# sdcard.net
KiCad netlist of a schematic drawn in EAGLE
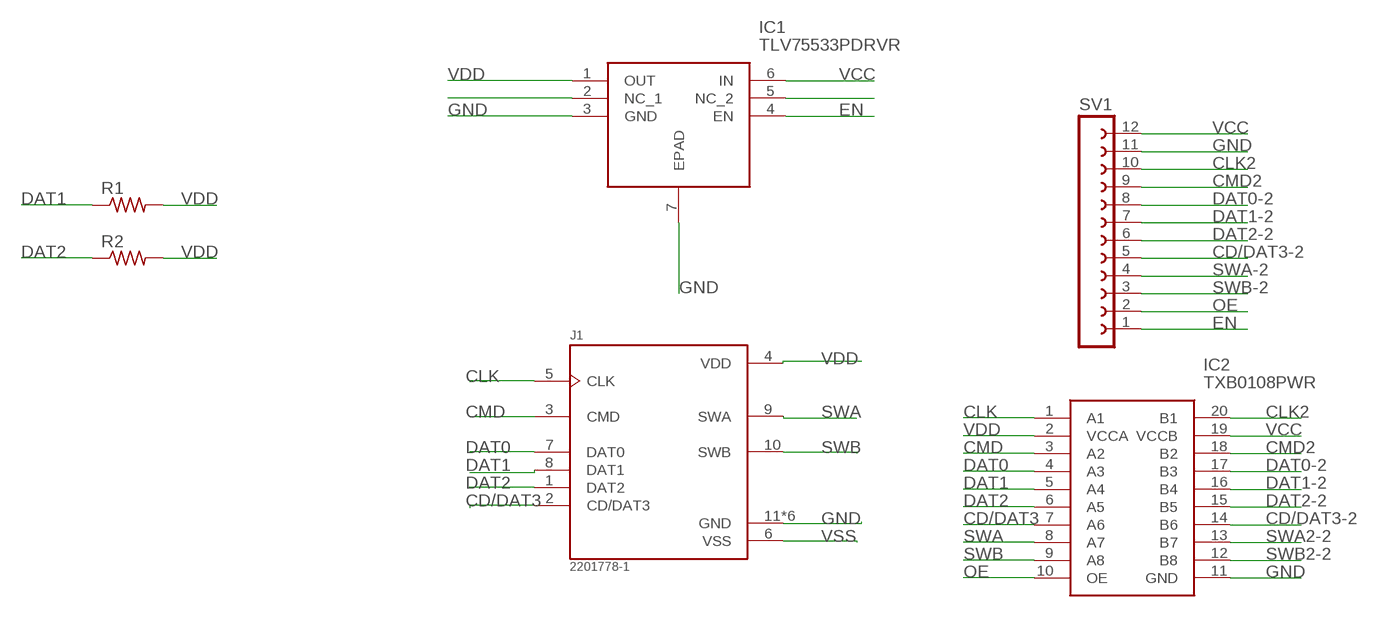
[diagram p0: schematic, sheet 1]

(export (version "E")
  (design (tool "Eeschema 10.0.6"))
  (components
    (comp (ref "IC1")
      (value "TLV75533PDRVR")
      (footprint "eagle-import:SON65P200X200X80-7N")
      (fields (field (name "MOUSER_PART_NUMBER") "595-TLV75533PDRVR"))
      (libsource (lib "eagle-import") (part "TLV75533PDRVR"))
    )
    (comp (ref "IC2")
      (value "TXB0108PWR")
      (footprint "eagle-import:SOP65P640X120-20N")
      (fields (field (name "MOUSER_PART_NUMBER") "595-TXB0108PWR") (field (name "RS_PART_NUMBER") "7094614P"))
      (libsource (lib "eagle-import") (part "TXB0108PWR"))
    )
    (comp (ref "J1")
      (value "2201778-1")
      (footprint "eagle-import:TE_2201778-1")
      (fields (field (name "MF") "TE Connectivity"))
      (libsource (lib "eagle-import") (part "2201778-1"))
    )
    (comp (ref "R1")
      (value "R-US_R0603")
      (footprint "eagle-import:R0603")
      (libsource (lib "eagle-import") (part "R-US_R0603"))
    )
    (comp (ref "R2")
      (value "R-US_R0603")
      (footprint "eagle-import:R0603")
      (libsource (lib "eagle-import") (part "R-US_R0603"))
    )
    (comp (ref "SV1")
      (value "FE12-1")
      (footprint "eagle-import:FE12")
      (libsource (lib "eagle-import") (part "FE12-1"))
    )
  )
  (nets
    (net (code "1") (name "/CD{slash}DAT3") (class "Default")
      (node (ref "IC2") (pin "7") (pinfunction "A6_7") (pintype "bidirectional"))
      (node (ref "J1") (pin "2") (pinfunction "CD/DAT3_2") (pintype "bidirectional"))
    )
    (net (code "2") (name "/CD{slash}DAT3-2") (class "Default")
      (node (ref "IC2") (pin "14") (pinfunction "B6_14") (pintype "bidirectional"))
      (node (ref "SV1") (pin "5") (pinfunction "5_5") (pintype "passive"))
    )
    (net (code "3") (name "/CLK") (class "Default")
      (node (ref "IC2") (pin "1") (pinfunction "A1_1") (pintype "bidirectional"))
      (node (ref "J1") (pin "5") (pinfunction "CLK_5") (pintype "input"))
    )
    (net (code "4") (name "/CLK2") (class "Default")
      (node (ref "IC2") (pin "20") (pinfunction "B1_20") (pintype "bidirectional"))
      (node (ref "SV1") (pin "10") (pinfunction "10_10") (pintype "passive"))
    )
    (net (code "5") (name "/CMD") (class "Default")
      (node (ref "IC2") (pin "3") (pinfunction "A2_3") (pintype "bidirectional"))
      (node (ref "J1") (pin "3") (pinfunction "CMD_3") (pintype "bidirectional"))
    )
    (net (code "6") (name "/CMD2") (class "Default")
      (node (ref "IC2") (pin "18") (pinfunction "B2_18") (pintype "bidirectional"))
      (node (ref "SV1") (pin "9") (pinfunction "9_9") (pintype "passive"))
    )
    (net (code "7") (name "/DAT0") (class "Default")
      (node (ref "IC2") (pin "4") (pinfunction "A3_4") (pintype "bidirectional"))
      (node (ref "J1") (pin "7") (pinfunction "DAT0_7") (pintype "bidirectional"))
    )
    (net (code "8") (name "/DAT0-2") (class "Default")
      (node (ref "IC2") (pin "17") (pinfunction "B3_17") (pintype "bidirectional"))
      (node (ref "SV1") (pin "8") (pinfunction "8_8") (pintype "passive"))
    )
    (net (code "9") (name "/DAT1") (class "Default")
      (node (ref "IC2") (pin "5") (pinfunction "A4_5") (pintype "bidirectional"))
      (node (ref "J1") (pin "8") (pinfunction "DAT1_8") (pintype "bidirectional"))
      (node (ref "R1") (pin "1") (pinfunction "1_1") (pintype "passive"))
    )
    (net (code "10") (name "/DAT1-2") (class "Default")
      (node (ref "IC2") (pin "16") (pinfunction "B4_16") (pintype "bidirectional"))
      (node (ref "SV1") (pin "7") (pinfunction "7_7") (pintype "passive"))
    )
    (net (code "11") (name "/DAT2") (class "Default")
      (node (ref "IC2") (pin "6") (pinfunction "A5_6") (pintype "bidirectional"))
      (node (ref "J1") (pin "1") (pinfunction "DAT2_1") (pintype "bidirectional"))
      (node (ref "R2") (pin "1") (pinfunction "1_1") (pintype "passive"))
    )
    (net (code "12") (name "/DAT2-2") (class "Default")
      (node (ref "IC2") (pin "15") (pinfunction "B5_15") (pintype "bidirectional"))
      (node (ref "SV1") (pin "6") (pinfunction "6_6") (pintype "passive"))
    )
    (net (code "13") (name "/EN") (class "Default")
      (node (ref "IC1") (pin "4") (pinfunction "EN_4") (pintype "bidirectional"))
      (node (ref "SV1") (pin "1") (pinfunction "1_1") (pintype "passive"))
    )
    (net (code "14") (name "/GND") (class "Default")
      (node (ref "IC1") (pin "3") (pinfunction "GND_3") (pintype "bidirectional"))
      (node (ref "IC1") (pin "7") (pinfunction "EPAD_7") (pintype "bidirectional"))
      (node (ref "IC2") (pin "11") (pinfunction "GND_11") (pintype "power_in"))
      (node (ref "J1") (pin "11") (pinfunction "GND_11") (pintype "power_in"))
      (node (ref "J1") (pin "12") (pinfunction "GND_12") (pintype "power_in"))
      (node (ref "J1") (pin "13") (pinfunction "GND_13") (pintype "power_in"))
      (node (ref "J1") (pin "14") (pinfunction "GND_14") (pintype "power_in"))
      (node (ref "J1") (pin "15") (pinfunction "GND_15") (pintype "power_in"))
      (node (ref "J1") (pin "16") (pinfunction "GND_16") (pintype "power_in"))
      (node (ref "SV1") (pin "11") (pinfunction "11_11") (pintype "passive"))
    )
    (net (code "15") (name "/OE") (class "Default")
      (node (ref "IC2") (pin "10") (pinfunction "OE_10") (pintype "bidirectional"))
      (node (ref "SV1") (pin "2") (pinfunction "2_2") (pintype "passive"))
    )
    (net (code "16") (name "/SWA") (class "Default")
      (node (ref "IC2") (pin "8") (pinfunction "A7_8") (pintype "bidirectional"))
      (node (ref "J1") (pin "9") (pinfunction "SWA_9") (pintype "passive"))
    )
    (net (code "17") (name "/SWA-2") (class "Default")
      (node (ref "SV1") (pin "4") (pinfunction "4_4") (pintype "passive"))
    )
    (net (code "18") (name "/SWA2-2") (class "Default")
      (node (ref "IC2") (pin "13") (pinfunction "B7_13") (pintype "bidirectional"))
    )
    (net (code "19") (name "/SWB") (class "Default")
      (node (ref "IC2") (pin "9") (pinfunction "A8_9") (pintype "bidirectional"))
      (node (ref "J1") (pin "10") (pinfunction "SWB_10") (pintype "passive"))
    )
    (net (code "20") (name "/SWB-2") (class "Default")
      (node (ref "SV1") (pin "3") (pinfunction "3_3") (pintype "passive"))
    )
    (net (code "21") (name "/SWB2-2") (class "Default")
      (node (ref "IC2") (pin "12") (pinfunction "B8_12") (pintype "bidirectional"))
    )
    (net (code "22") (name "/VCC") (class "Default")
      (node (ref "IC1") (pin "6") (pinfunction "IN_6") (pintype "bidirectional"))
      (node (ref "IC2") (pin "19") (pinfunction "VCCB_19") (pintype "power_in"))
      (node (ref "SV1") (pin "12") (pinfunction "12_12") (pintype "passive"))
    )
    (net (code "23") (name "/VDD") (class "Default")
      (node (ref "IC1") (pin "1") (pinfunction "OUT_1") (pintype "bidirectional"))
      (node (ref "IC2") (pin "2") (pinfunction "VCCA_2") (pintype "power_in"))
      (node (ref "J1") (pin "4") (pinfunction "VDD_4") (pintype "power_in"))
      (node (ref "R1") (pin "2") (pinfunction "2_2") (pintype "passive"))
      (node (ref "R2") (pin "2") (pinfunction "2_2") (pintype "passive"))
    )
    (net (code "24") (name "/VSS") (class "Default")
      (node (ref "J1") (pin "6") (pinfunction "VSS_6") (pintype "power_in"))
    )
    (net (code "25") (name "unconnected-(IC1-NC_1-Pad2)") (class "Default")
      (node (ref "IC1") (pin "2") (pinfunction "NC_1_2") (pintype "bidirectional"))
    )
    (net (code "26") (name "unconnected-(IC1-NC_2-Pad5)") (class "Default")
      (node (ref "IC1") (pin "5") (pinfunction "NC_2_5") (pintype "bidirectional"))
    )
  )
)
